# MCU.net
KiCad netlist of a schematic drawn in Altium Designer
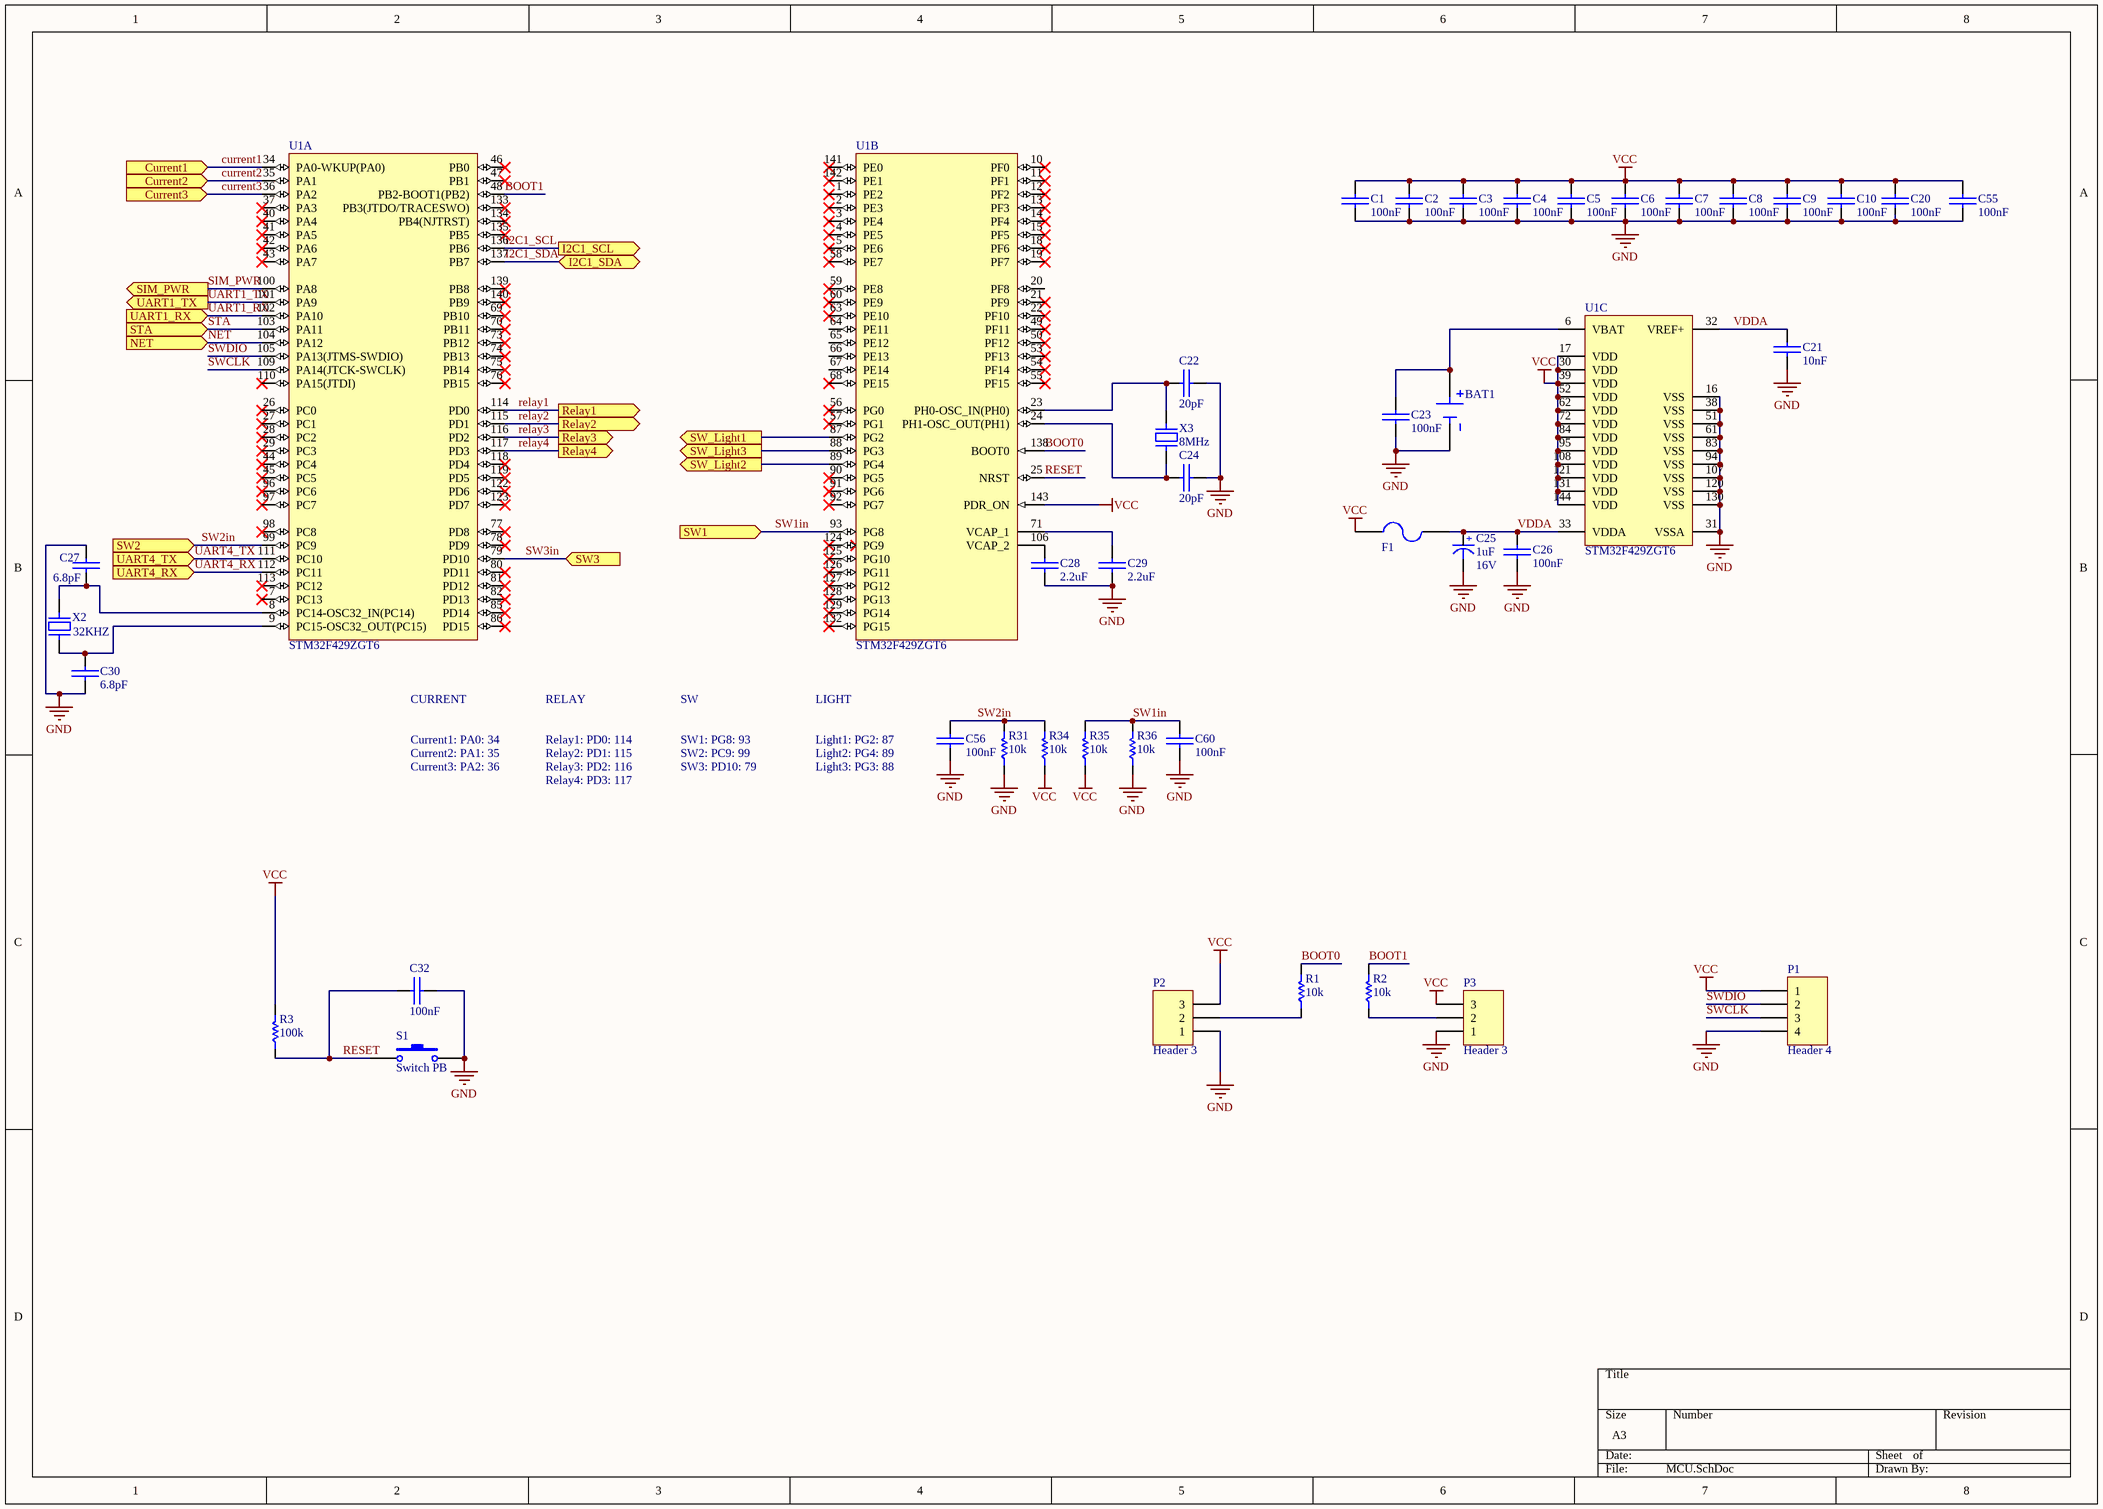
[diagram p0: MCU.SchDoc]

(export (version "E")
  (design (tool "Eeschema 10.0.6"))
  (components
    (comp (ref "BAT1")
      (value "BAT")
      (footprint "BAT_STAND")
      (description "BATTERY HOLDER COIN")
      (libsource (lib "SeyedMojtaba") (part "BAT"))
    )
    (comp (ref "C1")
      (value "100nF")
      (footprint "CAP 0603_1608")
      (description "Bipolar Capacitor")
      (fields (field (name "VOLTAGE") "100V") (field (name "DESIGNER") "Saeid Jorablo"))
      (libsource (lib "My_Library") (part "Cap-Bipolar"))
    )
    (comp (ref "C2")
      (value "100nF")
      (footprint "CAP 0603_1608")
      (description "Bipolar Capacitor")
      (fields (field (name "VOLTAGE") "100V") (field (name "DESIGNER") "Saeid Jorablo"))
      (libsource (lib "My_Library") (part "Cap-Bipolar"))
    )
    (comp (ref "C3")
      (value "100nF")
      (footprint "CAP 0603_1608")
      (description "Bipolar Capacitor")
      (fields (field (name "VOLTAGE") "100V") (field (name "DESIGNER") "Saeid Jorablo"))
      (libsource (lib "My_Library") (part "Cap-Bipolar"))
    )
    (comp (ref "C4")
      (value "100nF")
      (footprint "CAP 0603_1608")
      (description "Bipolar Capacitor")
      (fields (field (name "VOLTAGE") "100V") (field (name "DESIGNER") "Saeid Jorablo"))
      (libsource (lib "My_Library") (part "Cap-Bipolar"))
    )
    (comp (ref "C5")
      (value "100nF")
      (footprint "CAP 0603_1608")
      (description "Bipolar Capacitor")
      (fields (field (name "VOLTAGE") "100V") (field (name "DESIGNER") "Saeid Jorablo"))
      (libsource (lib "My_Library") (part "Cap-Bipolar"))
    )
    (comp (ref "C6")
      (value "100nF")
      (footprint "CAP 0603_1608")
      (description "Bipolar Capacitor")
      (fields (field (name "VOLTAGE") "100V") (field (name "DESIGNER") "Saeid Jorablo"))
      (libsource (lib "My_Library") (part "Cap-Bipolar"))
    )
    (comp (ref "C7")
      (value "100nF")
      (footprint "CAP 0603_1608")
      (description "Bipolar Capacitor")
      (fields (field (name "VOLTAGE") "100V") (field (name "DESIGNER") "Saeid Jorablo"))
      (libsource (lib "My_Library") (part "Cap-Bipolar"))
    )
    (comp (ref "C8")
      (value "100nF")
      (footprint "CAP 0603_1608")
      (description "Bipolar Capacitor")
      (fields (field (name "VOLTAGE") "100V") (field (name "DESIGNER") "Saeid Jorablo"))
      (libsource (lib "My_Library") (part "Cap-Bipolar"))
    )
    (comp (ref "C9")
      (value "100nF")
      (footprint "CAP 0603_1608")
      (description "Bipolar Capacitor")
      (fields (field (name "VOLTAGE") "100V") (field (name "DESIGNER") "Saeid Jorablo"))
      (libsource (lib "My_Library") (part "Cap-Bipolar"))
    )
    (comp (ref "C10")
      (value "100nF")
      (footprint "CAP 0603_1608")
      (description "Bipolar Capacitor")
      (fields (field (name "VOLTAGE") "100V") (field (name "DESIGNER") "Saeid Jorablo"))
      (libsource (lib "My_Library") (part "Cap-Bipolar"))
    )
    (comp (ref "C20")
      (value "100nF")
      (footprint "CAP 0603_1608")
      (description "Bipolar Capacitor")
      (fields (field (name "VOLTAGE") "100V") (field (name "DESIGNER") "Saeid Jorablo"))
      (libsource (lib "My_Library") (part "Cap-Bipolar"))
    )
    (comp (ref "C21")
      (value "10nF")
      (footprint "CAP 0603_1608")
      (description "Bipolar Capacitor")
      (fields (field (name "VOLTAGE") "100V") (field (name "DESIGNER") "Saeid Jorablo"))
      (libsource (lib "My_Library") (part "Cap-Bipolar"))
    )
    (comp (ref "C22")
      (value "20pF")
      (footprint "CAP 0805_2012")
      (description "Bipolar Capacitor")
      (fields (field (name "VOLTAGE") "100V") (field (name "DESIGNER") "Saeid Jorablo"))
      (libsource (lib "My_Library") (part "Cap-Bipolar"))
    )
    (comp (ref "C23")
      (value "100nF")
      (footprint "CAP 0603_1608")
      (description "Bipolar Capacitor")
      (fields (field (name "VOLTAGE") "100V") (field (name "DESIGNER") "Saeid Jorablo"))
      (libsource (lib "My_Library") (part "Cap-Bipolar"))
    )
    (comp (ref "C24")
      (value "20pF")
      (footprint "CAP 0805_2012")
      (description "Bipolar Capacitor")
      (fields (field (name "VOLTAGE") "100V") (field (name "DESIGNER") "Saeid Jorablo"))
      (libsource (lib "My_Library") (part "Cap-Bipolar"))
    )
    (comp (ref "C25")
      (value "1uF")
      (footprint "CAPP 1206 (3216X18L) Size A")
      (description "Polar Capacitor")
      (fields (field (name "VOLTAGE") "16V") (field (name "DESIGNER") "Saeid Jorablo"))
      (libsource (lib "My_Library") (part "Cap-Polar"))
    )
    (comp (ref "C26")
      (value "100nF")
      (footprint "CAP 0603_1608")
      (description "Bipolar Capacitor")
      (fields (field (name "VOLTAGE") "100V") (field (name "DESIGNER") "Saeid Jorablo"))
      (libsource (lib "My_Library") (part "Cap-Bipolar"))
    )
    (comp (ref "C27")
      (value "6.8pF")
      (footprint "CAP 0805_2012")
      (description "Bipolar Capacitor")
      (fields (field (name "VOLTAGE") "100V") (field (name "DESIGNER") "Saeid Jorablo"))
      (libsource (lib "My_Library") (part "Cap-Bipolar"))
    )
    (comp (ref "C28")
      (value "2.2uF")
      (footprint "CAP 0805_2012")
      (description "Bipolar Capacitor")
      (fields (field (name "VOLTAGE") "100V") (field (name "DESIGNER") "Saeid Jorablo"))
      (libsource (lib "My_Library") (part "Cap-Bipolar"))
    )
    (comp (ref "C29")
      (value "2.2uF")
      (footprint "CAP 0805_2012")
      (description "Bipolar Capacitor")
      (fields (field (name "VOLTAGE") "100V") (field (name "DESIGNER") "Saeid Jorablo"))
      (libsource (lib "My_Library") (part "Cap-Bipolar"))
    )
    (comp (ref "C30")
      (value "6.8pF")
      (footprint "CAP 0805_2012")
      (description "Bipolar Capacitor")
      (fields (field (name "VOLTAGE") "100V") (field (name "DESIGNER") "Saeid Jorablo"))
      (libsource (lib "My_Library") (part "Cap-Bipolar"))
    )
    (comp (ref "C32")
      (value "100nF")
      (footprint "CAP 0603_1608")
      (description "Bipolar Capacitor")
      (fields (field (name "VOLTAGE") "100V") (field (name "DESIGNER") "Saeid Jorablo"))
      (libsource (lib "My_Library") (part "Cap-Bipolar"))
    )
    (comp (ref "C55")
      (value "100nF")
      (footprint "CAP 0603_1608")
      (description "Bipolar Capacitor")
      (fields (field (name "VOLTAGE") "100V") (field (name "DESIGNER") "Saeid Jorablo"))
      (libsource (lib "My_Library") (part "Cap-Bipolar"))
    )
    (comp (ref "C56")
      (value "100nF")
      (footprint "CAP 0805_2012")
      (description "Bipolar Capacitor")
      (fields (field (name "VOLTAGE") "100V") (field (name "DESIGNER") "Saeid Jorablo"))
      (libsource (lib "My_Library") (part "Cap-Bipolar"))
    )
    (comp (ref "C60")
      (value "100nF")
      (footprint "CAP 0805_2012")
      (description "Bipolar Capacitor")
      (fields (field (name "VOLTAGE") "100V") (field (name "DESIGNER") "Saeid Jorablo"))
      (libsource (lib "My_Library") (part "Cap-Bipolar"))
    )
    (comp (ref "F1")
      (value "Ferrite Bead")
      (footprint "FUSE_0805")
      (libsource (lib "FUSE_FERRITE_VDR") (part "Fuse 0805"))
    )
    (comp (ref "P1")
      (value "Header 4")
      (footprint "HDR1X4")
      (description "Header, 4-Pin")
      (fields (field (name "PUBLISHER") "Altium Limited"))
      (libsource (lib "Miscellaneous Connectors") (part "Header 4"))
    )
    (comp (ref "P2")
      (value "Header 3")
      (footprint "HDR1X3")
      (description "Header, 3-Pin")
      (fields (field (name "PUBLISHER") "Altium Limited"))
      (libsource (lib "") (part "Header 3_1"))
    )
    (comp (ref "P3")
      (value "Header 3")
      (footprint "HDR1X3")
      (description "Header, 3-Pin")
      (fields (field (name "PUBLISHER") "Altium Limited"))
      (libsource (lib "Miscellaneous Connectors") (part "Header 3"))
    )
    (comp (ref "R1")
      (value "10k")
      (footprint "RES 0805_2012")
      (description "Resistor")
      (libsource (lib "My_Library") (part "Resistor"))
    )
    (comp (ref "R2")
      (value "10k")
      (footprint "RES 0805_2012")
      (description "Resistor")
      (libsource (lib "My_Library") (part "Resistor"))
    )
    (comp (ref "R3")
      (value "100k")
      (footprint "RES 0805_2012")
      (description "Resistor")
      (libsource (lib "My_Library") (part "Resistor"))
    )
    (comp (ref "R31")
      (value "10k")
      (footprint "RES 0805_2012")
      (description "Resistor")
      (libsource (lib "My_Library") (part "Resistor"))
    )
    (comp (ref "R34")
      (value "10k")
      (footprint "RES 0805_2012")
      (description "Resistor")
      (libsource (lib "My_Library") (part "Resistor"))
    )
    (comp (ref "R35")
      (value "10k")
      (footprint "RES 0805_2012")
      (description "Resistor")
      (libsource (lib "My_Library") (part "Resistor"))
    )
    (comp (ref "R36")
      (value "10k")
      (footprint "RES 0805_2012")
      (description "Resistor")
      (libsource (lib "My_Library") (part "Resistor"))
    )
    (comp (ref "S1")
      (value "Switch PB")
      (footprint "Switch - Push to On")
      (description "Push Button Switch")
      (libsource (lib "My_Library") (part "Switch PB"))
    )
    (comp (ref "U1")
      (value "STM32F429ZGT6")
      (footprint "LQFP144")
      (fields (field (name "MANUFACTURER") "STMicroelectronics"))
      (libsource (lib "MCU_MPU") (part "STM32F429ZGT6"))
    )
    (comp (ref "X2")
      (value "32KHZ")
      (footprint "IND 1206_3216")
      (description "SMT Crystal")
      (libsource (lib "Xtal") (part "Crystal HC-49S SMD"))
    )
    (comp (ref "X3")
      (value "~")
      (footprint "XTAL THD HC49")
      (description "SMT Crystal")
      (fields (field (name "PARAMETER 1") "8MHz"))
      (libsource (lib "CRYSTAL") (part "Crystal THD HC49"))
    )
  )
  (nets
    (net (code "1") (name "/BOOT0") (class "Default")
      (node (ref "R1") (pin "2") (pinfunction "2_2") (pintype "passive"))
      (node (ref "U1") (pin "138") (pinfunction "BOOT0_138") (pintype "input"))
    )
    (net (code "2") (name "/BOOT1") (class "Default")
      (node (ref "R2") (pin "2") (pinfunction "2_2") (pintype "passive"))
      (node (ref "U1") (pin "48") (pinfunction "PB2-BOOT1(PB2)_48") (pintype "bidirectional"))
    )
    (net (code "3") (name "/I2C1_SCL") (class "Default")
      (node (ref "U1") (pin "136") (pinfunction "PB6_136") (pintype "bidirectional"))
    )
    (net (code "4") (name "/I2C1_SDA") (class "Default")
      (node (ref "U1") (pin "137") (pinfunction "PB7_137") (pintype "bidirectional"))
    )
    (net (code "5") (name "/NET") (class "Default")
      (node (ref "U1") (pin "104") (pinfunction "PA12_104") (pintype "bidirectional"))
    )
    (net (code "6") (name "/RESET") (class "Default")
      (node (ref "C32") (pin "2") (pinfunction "-_2") (pintype "passive"))
      (node (ref "R3") (pin "1") (pinfunction "1_1") (pintype "passive"))
      (node (ref "S1") (pin "1") (pinfunction "1_1") (pintype "passive"))
      (node (ref "U1") (pin "25") (pinfunction "NRST_25") (pintype "bidirectional"))
    )
    (net (code "7") (name "/SIM_PWR") (class "Default")
      (node (ref "U1") (pin "100") (pinfunction "PA8_100") (pintype "bidirectional"))
    )
    (net (code "8") (name "/STA") (class "Default")
      (node (ref "U1") (pin "103") (pinfunction "PA11_103") (pintype "bidirectional"))
    )
    (net (code "9") (name "/SW1in") (class "Default")
      (node (ref "C60") (pin "2") (pinfunction "-_2") (pintype "passive"))
      (node (ref "R35") (pin "2") (pinfunction "2_2") (pintype "passive"))
      (node (ref "R36") (pin "2") (pinfunction "2_2") (pintype "passive"))
      (node (ref "U1") (pin "93") (pinfunction "PG8_93") (pintype "bidirectional"))
    )
    (net (code "10") (name "/SW2in") (class "Default")
      (node (ref "C56") (pin "2") (pinfunction "-_2") (pintype "passive"))
      (node (ref "R31") (pin "2") (pinfunction "2_2") (pintype "passive"))
      (node (ref "R34") (pin "2") (pinfunction "2_2") (pintype "passive"))
      (node (ref "U1") (pin "99") (pinfunction "PC9_99") (pintype "bidirectional"))
    )
    (net (code "11") (name "/SW3in") (class "Default")
      (node (ref "U1") (pin "79") (pinfunction "PD10_79") (pintype "bidirectional"))
    )
    (net (code "12") (name "/SWCLK") (class "Default")
      (node (ref "P1") (pin "3") (pinfunction "3_3") (pintype "passive"))
      (node (ref "U1") (pin "109") (pinfunction "PA14(JTCK-SWCLK)_109") (pintype "bidirectional"))
    )
    (net (code "13") (name "/SWDIO") (class "Default")
      (node (ref "P1") (pin "2") (pinfunction "2_2") (pintype "passive"))
      (node (ref "U1") (pin "105") (pinfunction "PA13(JTMS-SWDIO)_105") (pintype "bidirectional"))
    )
    (net (code "14") (name "/SW_Light1") (class "Default")
      (node (ref "U1") (pin "87") (pinfunction "PG2_87") (pintype "bidirectional"))
    )
    (net (code "15") (name "/SW_Light2") (class "Default")
      (node (ref "U1") (pin "89") (pinfunction "PG4_89") (pintype "bidirectional"))
    )
    (net (code "16") (name "/SW_Light3") (class "Default")
      (node (ref "U1") (pin "88") (pinfunction "PG3_88") (pintype "bidirectional"))
    )
    (net (code "17") (name "/UART1_RX") (class "Default")
      (node (ref "U1") (pin "102") (pinfunction "PA10_102") (pintype "bidirectional"))
    )
    (net (code "18") (name "/UART1_TX") (class "Default")
      (node (ref "U1") (pin "101") (pinfunction "PA9_101") (pintype "bidirectional"))
    )
    (net (code "19") (name "/UART4_RX") (class "Default")
      (node (ref "U1") (pin "112") (pinfunction "PC11_112") (pintype "bidirectional"))
    )
    (net (code "20") (name "/UART4_TX") (class "Default")
      (node (ref "U1") (pin "111") (pinfunction "PC10_111") (pintype "bidirectional"))
    )
    (net (code "21") (name "/VDDA") (class "Default")
      (node (ref "C21") (pin "2") (pinfunction "-_2") (pintype "passive"))
      (node (ref "C25") (pin "1") (pinfunction "+_1") (pintype "passive"))
      (node (ref "C26") (pin "2") (pinfunction "-_2") (pintype "passive"))
      (node (ref "F1") (pin "2") (pinfunction "2_2") (pintype "passive"))
      (node (ref "U1") (pin "32") (pinfunction "VREF+_32") (pintype "power_in"))
      (node (ref "U1") (pin "33") (pinfunction "VDDA_33") (pintype "power_in"))
    )
    (net (code "22") (name "/current1") (class "Default")
      (node (ref "U1") (pin "34") (pinfunction "PA0-WKUP(PA0)_34") (pintype "bidirectional"))
    )
    (net (code "23") (name "/current2") (class "Default")
      (node (ref "U1") (pin "35") (pinfunction "PA1_35") (pintype "bidirectional"))
    )
    (net (code "24") (name "/current3") (class "Default")
      (node (ref "U1") (pin "36") (pinfunction "PA2_36") (pintype "bidirectional"))
    )
    (net (code "25") (name "/relay1") (class "Default")
      (node (ref "U1") (pin "114") (pinfunction "PD0_114") (pintype "bidirectional"))
    )
    (net (code "26") (name "/relay2") (class "Default")
      (node (ref "U1") (pin "115") (pinfunction "PD1_115") (pintype "bidirectional"))
    )
    (net (code "27") (name "/relay3") (class "Default")
      (node (ref "U1") (pin "116") (pinfunction "PD2_116") (pintype "bidirectional"))
    )
    (net (code "28") (name "/relay4") (class "Default")
      (node (ref "U1") (pin "117") (pinfunction "PD3_117") (pintype "bidirectional"))
    )
    (net (code "29") (name "GND") (class "Default")
      (node (ref "BAT1") (pin "NEG") (pinfunction "NEG_NEG") (pintype "power_in"))
      (node (ref "C1") (pin "1") (pinfunction "+_1") (pintype "passive"))
      (node (ref "C10") (pin "1") (pinfunction "+_1") (pintype "passive"))
      (node (ref "C2") (pin "1") (pinfunction "+_1") (pintype "passive"))
      (node (ref "C20") (pin "1") (pinfunction "+_1") (pintype "passive"))
      (node (ref "C21") (pin "1") (pinfunction "+_1") (pintype "passive"))
      (node (ref "C22") (pin "1") (pinfunction "+_1") (pintype "passive"))
      (node (ref "C23") (pin "1") (pinfunction "+_1") (pintype "passive"))
      (node (ref "C24") (pin "1") (pinfunction "+_1") (pintype "passive"))
      (node (ref "C25") (pin "2") (pinfunction "-_2") (pintype "passive"))
      (node (ref "C26") (pin "1") (pinfunction "+_1") (pintype "passive"))
      (node (ref "C27") (pin "1") (pinfunction "+_1") (pintype "passive"))
      (node (ref "C28") (pin "1") (pinfunction "+_1") (pintype "passive"))
      (node (ref "C29") (pin "1") (pinfunction "+_1") (pintype "passive"))
      (node (ref "C3") (pin "1") (pinfunction "+_1") (pintype "passive"))
      (node (ref "C30") (pin "2") (pinfunction "-_2") (pintype "passive"))
      (node (ref "C32") (pin "1") (pinfunction "+_1") (pintype "passive"))
      (node (ref "C4") (pin "1") (pinfunction "+_1") (pintype "passive"))
      (node (ref "C5") (pin "1") (pinfunction "+_1") (pintype "passive"))
      (node (ref "C55") (pin "1") (pinfunction "+_1") (pintype "passive"))
      (node (ref "C56") (pin "1") (pinfunction "+_1") (pintype "passive"))
      (node (ref "C6") (pin "1") (pinfunction "+_1") (pintype "passive"))
      (node (ref "C60") (pin "1") (pinfunction "+_1") (pintype "passive"))
      (node (ref "C7") (pin "1") (pinfunction "+_1") (pintype "passive"))
      (node (ref "C8") (pin "1") (pinfunction "+_1") (pintype "passive"))
      (node (ref "C9") (pin "1") (pinfunction "+_1") (pintype "passive"))
      (node (ref "P1") (pin "4") (pinfunction "4_4") (pintype "passive"))
      (node (ref "P2") (pin "1") (pinfunction "1_1") (pintype "passive"))
      (node (ref "P3") (pin "1") (pinfunction "1_1") (pintype "passive"))
      (node (ref "R31") (pin "1") (pinfunction "1_1") (pintype "passive"))
      (node (ref "R36") (pin "1") (pinfunction "1_1") (pintype "passive"))
      (node (ref "S1") (pin "2") (pinfunction "2_2") (pintype "passive"))
      (node (ref "U1") (pin "107") (pinfunction "VSS_107") (pintype "power_in"))
      (node (ref "U1") (pin "120") (pinfunction "VSS_120") (pintype "power_in"))
      (node (ref "U1") (pin "130") (pinfunction "VSS_130") (pintype "power_in"))
      (node (ref "U1") (pin "16") (pinfunction "VSS_16") (pintype "power_in"))
      (node (ref "U1") (pin "31") (pinfunction "VSSA_31") (pintype "power_in"))
      (node (ref "U1") (pin "38") (pinfunction "VSS_38") (pintype "power_in"))
      (node (ref "U1") (pin "51") (pinfunction "VSS_51") (pintype "power_in"))
      (node (ref "U1") (pin "61") (pinfunction "VSS_61") (pintype "power_in"))
      (node (ref "U1") (pin "83") (pinfunction "VSS_83") (pintype "power_in"))
      (node (ref "U1") (pin "94") (pinfunction "VSS_94") (pintype "power_in"))
    )
    (net (code "30") (name "Net-(C22--)") (class "Default")
      (node (ref "C22") (pin "2") (pinfunction "-_2") (pintype "passive"))
      (node (ref "U1") (pin "23") (pinfunction "PH0-OSC_IN(PH0)_23") (pintype "bidirectional"))
      (node (ref "X3") (pin "2") (pinfunction "2_2") (pintype "passive"))
    )
    (net (code "31") (name "Net-(C23--)") (class "Default")
      (node (ref "BAT1") (pin "S+1") (pinfunction "POS_S+1") (pintype "passive"))
      (node (ref "BAT1") (pin "S+2") (pinfunction "POS_S+2") (pintype "power_in"))
      (node (ref "C23") (pin "2") (pinfunction "-_2") (pintype "passive"))
      (node (ref "U1") (pin "6") (pinfunction "VBAT_6") (pintype "power_in"))
    )
    (net (code "32") (name "Net-(C24--)") (class "Default")
      (node (ref "C24") (pin "2") (pinfunction "-_2") (pintype "passive"))
      (node (ref "U1") (pin "24") (pinfunction "PH1-OSC_OUT(PH1)_24") (pintype "bidirectional"))
      (node (ref "X3") (pin "1") (pinfunction "1_1") (pintype "passive"))
    )
    (net (code "33") (name "Net-(C27--)") (class "Default")
      (node (ref "C27") (pin "2") (pinfunction "-_2") (pintype "passive"))
      (node (ref "U1") (pin "8") (pinfunction "PC14-OSC32_IN(PC14)_8") (pintype "bidirectional"))
      (node (ref "X2") (pin "2") (pinfunction "2_2") (pintype "passive"))
    )
    (net (code "34") (name "Net-(C28--)") (class "Default")
      (node (ref "C28") (pin "2") (pinfunction "-_2") (pintype "passive"))
      (node (ref "U1") (pin "106") (pinfunction "VCAP_2_106") (pintype "power_in"))
    )
    (net (code "35") (name "Net-(C29--)") (class "Default")
      (node (ref "C29") (pin "2") (pinfunction "-_2") (pintype "passive"))
      (node (ref "U1") (pin "71") (pinfunction "VCAP_1_71") (pintype "power_in"))
    )
    (net (code "36") (name "Net-(C30-+)") (class "Default")
      (node (ref "C30") (pin "1") (pinfunction "+_1") (pintype "passive"))
      (node (ref "U1") (pin "9") (pinfunction "PC15-OSC32_OUT(PC15)_9") (pintype "bidirectional"))
      (node (ref "X2") (pin "1") (pinfunction "1_1") (pintype "passive"))
    )
    (net (code "37") (name "Net-(P2-Pad2)") (class "Default")
      (node (ref "P2") (pin "2") (pinfunction "2_2") (pintype "passive"))
      (node (ref "R1") (pin "1") (pinfunction "1_1") (pintype "passive"))
    )
    (net (code "38") (name "Net-(P3-Pad2)") (class "Default")
      (node (ref "P3") (pin "2") (pinfunction "2_2") (pintype "passive"))
      (node (ref "R2") (pin "1") (pinfunction "1_1") (pintype "passive"))
    )
    (net (code "39") (name "VCC") (class "Default")
      (node (ref "C1") (pin "2") (pinfunction "-_2") (pintype "passive"))
      (node (ref "C10") (pin "2") (pinfunction "-_2") (pintype "passive"))
      (node (ref "C2") (pin "2") (pinfunction "-_2") (pintype "passive"))
      (node (ref "C20") (pin "2") (pinfunction "-_2") (pintype "passive"))
      (node (ref "C3") (pin "2") (pinfunction "-_2") (pintype "passive"))
      (node (ref "C4") (pin "2") (pinfunction "-_2") (pintype "passive"))
      (node (ref "C5") (pin "2") (pinfunction "-_2") (pintype "passive"))
      (node (ref "C55") (pin "2") (pinfunction "-_2") (pintype "passive"))
      (node (ref "C6") (pin "2") (pinfunction "-_2") (pintype "passive"))
      (node (ref "C7") (pin "2") (pinfunction "-_2") (pintype "passive"))
      (node (ref "C8") (pin "2") (pinfunction "-_2") (pintype "passive"))
      (node (ref "C9") (pin "2") (pinfunction "-_2") (pintype "passive"))
      (node (ref "F1") (pin "1") (pinfunction "1_1") (pintype "passive"))
      (node (ref "P1") (pin "1") (pinfunction "1_1") (pintype "passive"))
      (node (ref "P2") (pin "3") (pinfunction "3_3") (pintype "passive"))
      (node (ref "P3") (pin "3") (pinfunction "3_3") (pintype "passive"))
      (node (ref "R3") (pin "2") (pinfunction "2_2") (pintype "passive"))
      (node (ref "R34") (pin "1") (pinfunction "1_1") (pintype "passive"))
      (node (ref "R35") (pin "1") (pinfunction "1_1") (pintype "passive"))
      (node (ref "U1") (pin "108") (pinfunction "VDD_108") (pintype "power_in"))
      (node (ref "U1") (pin "121") (pinfunction "VDD_121") (pintype "power_in"))
      (node (ref "U1") (pin "131") (pinfunction "VDD_131") (pintype "power_in"))
      (node (ref "U1") (pin "143") (pinfunction "PDR_ON_143") (pintype "input"))
      (node (ref "U1") (pin "144") (pinfunction "VDD_144") (pintype "power_in"))
      (node (ref "U1") (pin "17") (pinfunction "VDD_17") (pintype "power_in"))
      (node (ref "U1") (pin "30") (pinfunction "VDD_30") (pintype "power_in"))
      (node (ref "U1") (pin "39") (pinfunction "VDD_39") (pintype "power_in"))
      (node (ref "U1") (pin "52") (pinfunction "VDD_52") (pintype "power_in"))
      (node (ref "U1") (pin "62") (pinfunction "VDD_62") (pintype "power_in"))
      (node (ref "U1") (pin "72") (pinfunction "VDD_72") (pintype "power_in"))
      (node (ref "U1") (pin "84") (pinfunction "VDD_84") (pintype "power_in"))
      (node (ref "U1") (pin "95") (pinfunction "VDD_95") (pintype "power_in"))
    )
    (net (code "40") (name "unconnected-(U1A-PA3-Pad37)") (class "Default")
      (node (ref "U1") (pin "37") (pinfunction "PA3_37") (pintype "bidirectional+no_connect"))
    )
    (net (code "41") (name "unconnected-(U1A-PA4-Pad40)") (class "Default")
      (node (ref "U1") (pin "40") (pinfunction "PA4_40") (pintype "bidirectional+no_connect"))
    )
    (net (code "42") (name "unconnected-(U1A-PA5-Pad41)") (class "Default")
      (node (ref "U1") (pin "41") (pinfunction "PA5_41") (pintype "bidirectional+no_connect"))
    )
    (net (code "43") (name "unconnected-(U1A-PA6-Pad42)") (class "Default")
      (node (ref "U1") (pin "42") (pinfunction "PA6_42") (pintype "bidirectional+no_connect"))
    )
    (net (code "44") (name "unconnected-(U1A-PA7-Pad43)") (class "Default")
      (node (ref "U1") (pin "43") (pinfunction "PA7_43") (pintype "bidirectional+no_connect"))
    )
    (net (code "45") (name "unconnected-(U1A-PA15(JTDI)-Pad110)") (class "Default")
      (node (ref "U1") (pin "110") (pinfunction "PA15(JTDI)_110") (pintype "bidirectional+no_connect"))
    )
    (net (code "46") (name "unconnected-(U1A-PB0-Pad46)") (class "Default")
      (node (ref "U1") (pin "46") (pinfunction "PB0_46") (pintype "bidirectional+no_connect"))
    )
    (net (code "47") (name "unconnected-(U1A-PB1-Pad47)") (class "Default")
      (node (ref "U1") (pin "47") (pinfunction "PB1_47") (pintype "bidirectional+no_connect"))
    )
    (net (code "48") (name "unconnected-(U1A-PB3(JTDO{slash}TRACESWO)-Pad133)") (class "Default")
      (node (ref "U1") (pin "133") (pinfunction "PB3(JTDO/TRACESWO)_133") (pintype "bidirectional+no_connect"))
    )
    (net (code "49") (name "unconnected-(U1A-PB4(NJTRST)-Pad134)") (class "Default")
      (node (ref "U1") (pin "134") (pinfunction "PB4(NJTRST)_134") (pintype "bidirectional+no_connect"))
    )
    (net (code "50") (name "unconnected-(U1A-PB5-Pad135)") (class "Default")
      (node (ref "U1") (pin "135") (pinfunction "PB5_135") (pintype "bidirectional+no_connect"))
    )
    (net (code "51") (name "unconnected-(U1A-PB8-Pad139)") (class "Default")
      (node (ref "U1") (pin "139") (pinfunction "PB8_139") (pintype "bidirectional+no_connect"))
    )
    (net (code "52") (name "unconnected-(U1A-PB9-Pad140)") (class "Default")
      (node (ref "U1") (pin "140") (pinfunction "PB9_140") (pintype "bidirectional+no_connect"))
    )
    (net (code "53") (name "unconnected-(U1A-PB10-Pad69)") (class "Default")
      (node (ref "U1") (pin "69") (pinfunction "PB10_69") (pintype "bidirectional+no_connect"))
    )
    (net (code "54") (name "unconnected-(U1A-PB11-Pad70)") (class "Default")
      (node (ref "U1") (pin "70") (pinfunction "PB11_70") (pintype "bidirectional+no_connect"))
    )
    (net (code "55") (name "unconnected-(U1A-PB12-Pad73)") (class "Default")
      (node (ref "U1") (pin "73") (pinfunction "PB12_73") (pintype "bidirectional+no_connect"))
    )
    (net (code "56") (name "unconnected-(U1A-PB13-Pad74)") (class "Default")
      (node (ref "U1") (pin "74") (pinfunction "PB13_74") (pintype "bidirectional+no_connect"))
    )
    (net (code "57") (name "unconnected-(U1A-PB14-Pad75)") (class "Default")
      (node (ref "U1") (pin "75") (pinfunction "PB14_75") (pintype "bidirectional+no_connect"))
    )
    (net (code "58") (name "unconnected-(U1A-PB15-Pad76)") (class "Default")
      (node (ref "U1") (pin "76") (pinfunction "PB15_76") (pintype "bidirectional+no_connect"))
    )
    (net (code "59") (name "unconnected-(U1A-PC0-Pad26)") (class "Default")
      (node (ref "U1") (pin "26") (pinfunction "PC0_26") (pintype "bidirectional+no_connect"))
    )
    (net (code "60") (name "unconnected-(U1A-PC1-Pad27)") (class "Default")
      (node (ref "U1") (pin "27") (pinfunction "PC1_27") (pintype "bidirectional+no_connect"))
    )
    (net (code "61") (name "unconnected-(U1A-PC2-Pad28)") (class "Default")
      (node (ref "U1") (pin "28") (pinfunction "PC2_28") (pintype "bidirectional+no_connect"))
    )
    (net (code "62") (name "unconnected-(U1A-PC3-Pad29)") (class "Default")
      (node (ref "U1") (pin "29") (pinfunction "PC3_29") (pintype "bidirectional+no_connect"))
    )
    (net (code "63") (name "unconnected-(U1A-PC4-Pad44)") (class "Default")
      (node (ref "U1") (pin "44") (pinfunction "PC4_44") (pintype "bidirectional+no_connect"))
    )
    (net (code "64") (name "unconnected-(U1A-PC5-Pad45)") (class "Default")
      (node (ref "U1") (pin "45") (pinfunction "PC5_45") (pintype "bidirectional+no_connect"))
    )
    (net (code "65") (name "unconnected-(U1A-PC6-Pad96)") (class "Default")
      (node (ref "U1") (pin "96") (pinfunction "PC6_96") (pintype "bidirectional+no_connect"))
    )
    (net (code "66") (name "unconnected-(U1A-PC7-Pad97)") (class "Default")
      (node (ref "U1") (pin "97") (pinfunction "PC7_97") (pintype "bidirectional+no_connect"))
    )
    (net (code "67") (name "unconnected-(U1A-PC8-Pad98)") (class "Default")
      (node (ref "U1") (pin "98") (pinfunction "PC8_98") (pintype "bidirectional+no_connect"))
    )
    (net (code "68") (name "unconnected-(U1A-PC12-Pad113)") (class "Default")
      (node (ref "U1") (pin "113") (pinfunction "PC12_113") (pintype "bidirectional+no_connect"))
    )
    (net (code "69") (name "unconnected-(U1A-PC13-Pad7)") (class "Default")
      (node (ref "U1") (pin "7") (pinfunction "PC13_7") (pintype "bidirectional+no_connect"))
    )
    (net (code "70") (name "unconnected-(U1A-PD4-Pad118)") (class "Default")
      (node (ref "U1") (pin "118") (pinfunction "PD4_118") (pintype "bidirectional+no_connect"))
    )
    (net (code "71") (name "unconnected-(U1A-PD5-Pad119)") (class "Default")
      (node (ref "U1") (pin "119") (pinfunction "PD5_119") (pintype "bidirectional+no_connect"))
    )
    (net (code "72") (name "unconnected-(U1A-PD6-Pad122)") (class "Default")
      (node (ref "U1") (pin "122") (pinfunction "PD6_122") (pintype "bidirectional+no_connect"))
    )
    (net (code "73") (name "unconnected-(U1A-PD7-Pad123)") (class "Default")
      (node (ref "U1") (pin "123") (pinfunction "PD7_123") (pintype "bidirectional+no_connect"))
    )
    (net (code "74") (name "unconnected-(U1A-PD8-Pad77)") (class "Default")
      (node (ref "U1") (pin "77") (pinfunction "PD8_77") (pintype "bidirectional+no_connect"))
    )
    (net (code "75") (name "unconnected-(U1A-PD9-Pad78)") (class "Default")
      (node (ref "U1") (pin "78") (pinfunction "PD9_78") (pintype "bidirectional+no_connect"))
    )
    (net (code "76") (name "unconnected-(U1A-PD11-Pad80)") (class "Default")
      (node (ref "U1") (pin "80") (pinfunction "PD11_80") (pintype "bidirectional+no_connect"))
    )
    (net (code "77") (name "unconnected-(U1A-PD12-Pad81)") (class "Default")
      (node (ref "U1") (pin "81") (pinfunction "PD12_81") (pintype "bidirectional+no_connect"))
    )
    (net (code "78") (name "unconnected-(U1A-PD13-Pad82)") (class "Default")
      (node (ref "U1") (pin "82") (pinfunction "PD13_82") (pintype "bidirectional+no_connect"))
    )
    (net (code "79") (name "unconnected-(U1A-PD14-Pad85)") (class "Default")
      (node (ref "U1") (pin "85") (pinfunction "PD14_85") (pintype "bidirectional+no_connect"))
    )
    (net (code "80") (name "unconnected-(U1A-PD15-Pad86)") (class "Default")
      (node (ref "U1") (pin "86") (pinfunction "PD15_86") (pintype "bidirectional+no_connect"))
    )
    (net (code "81") (name "unconnected-(U1B-PE0-Pad141)") (class "Default")
      (node (ref "U1") (pin "141") (pinfunction "PE0_141") (pintype "bidirectional+no_connect"))
    )
    (net (code "82") (name "unconnected-(U1B-PE1-Pad142)") (class "Default")
      (node (ref "U1") (pin "142") (pinfunction "PE1_142") (pintype "bidirectional+no_connect"))
    )
    (net (code "83") (name "unconnected-(U1B-PE2-Pad1)") (class "Default")
      (node (ref "U1") (pin "1") (pinfunction "PE2_1") (pintype "bidirectional+no_connect"))
    )
    (net (code "84") (name "unconnected-(U1B-PE3-Pad2)") (class "Default")
      (node (ref "U1") (pin "2") (pinfunction "PE3_2") (pintype "bidirectional+no_connect"))
    )
    (net (code "85") (name "unconnected-(U1B-PE4-Pad3)") (class "Default")
      (node (ref "U1") (pin "3") (pinfunction "PE4_3") (pintype "bidirectional+no_connect"))
    )
    (net (code "86") (name "unconnected-(U1B-PE5-Pad4)") (class "Default")
      (node (ref "U1") (pin "4") (pinfunction "PE5_4") (pintype "bidirectional+no_connect"))
    )
    (net (code "87") (name "unconnected-(U1B-PE6-Pad5)") (class "Default")
      (node (ref "U1") (pin "5") (pinfunction "PE6_5") (pintype "bidirectional+no_connect"))
    )
    (net (code "88") (name "unconnected-(U1B-PE7-Pad58)") (class "Default")
      (node (ref "U1") (pin "58") (pinfunction "PE7_58") (pintype "bidirectional+no_connect"))
    )
    (net (code "89") (name "unconnected-(U1B-PE8-Pad59)") (class "Default")
      (node (ref "U1") (pin "59") (pinfunction "PE8_59") (pintype "bidirectional+no_connect"))
    )
    (net (code "90") (name "unconnected-(U1B-PE9-Pad60)") (class "Default")
      (node (ref "U1") (pin "60") (pinfunction "PE9_60") (pintype "bidirectional+no_connect"))
    )
    (net (code "91") (name "unconnected-(U1B-PE10-Pad63)") (class "Default")
      (node (ref "U1") (pin "63") (pinfunction "PE10_63") (pintype "bidirectional+no_connect"))
    )
    (net (code "92") (name "unconnected-(U1B-PE11-Pad64)") (class "Default")
      (node (ref "U1") (pin "64") (pinfunction "PE11_64") (pintype "bidirectional"))
    )
    (net (code "93") (name "unconnected-(U1B-PE12-Pad65)") (class "Default")
      (node (ref "U1") (pin "65") (pinfunction "PE12_65") (pintype "bidirectional"))
    )
    (net (code "94") (name "unconnected-(U1B-PE13-Pad66)") (class "Default")
      (node (ref "U1") (pin "66") (pinfunction "PE13_66") (pintype "bidirectional"))
    )
    (net (code "95") (name "unconnected-(U1B-PE14-Pad67)") (class "Default")
      (node (ref "U1") (pin "67") (pinfunction "PE14_67") (pintype "bidirectional"))
    )
    (net (code "96") (name "unconnected-(U1B-PE15-Pad68)") (class "Default")
      (node (ref "U1") (pin "68") (pinfunction "PE15_68") (pintype "bidirectional+no_connect"))
    )
    (net (code "97") (name "unconnected-(U1B-PF0-Pad10)") (class "Default")
      (node (ref "U1") (pin "10") (pinfunction "PF0_10") (pintype "bidirectional+no_connect"))
    )
    (net (code "98") (name "unconnected-(U1B-PF1-Pad11)") (class "Default")
      (node (ref "U1") (pin "11") (pinfunction "PF1_11") (pintype "bidirectional+no_connect"))
    )
    (net (code "99") (name "unconnected-(U1B-PF2-Pad12)") (class "Default")
      (node (ref "U1") (pin "12") (pinfunction "PF2_12") (pintype "bidirectional+no_connect"))
    )
    (net (code "100") (name "unconnected-(U1B-PF3-Pad13)") (class "Default")
      (node (ref "U1") (pin "13") (pinfunction "PF3_13") (pintype "bidirectional+no_connect"))
    )
    (net (code "101") (name "unconnected-(U1B-PF4-Pad14)") (class "Default")
      (node (ref "U1") (pin "14") (pinfunction "PF4_14") (pintype "bidirectional+no_connect"))
    )
    (net (code "102") (name "unconnected-(U1B-PF5-Pad15)") (class "Default")
      (node (ref "U1") (pin "15") (pinfunction "PF5_15") (pintype "bidirectional+no_connect"))
    )
    (net (code "103") (name "unconnected-(U1B-PF6-Pad18)") (class "Default")
      (node (ref "U1") (pin "18") (pinfunction "PF6_18") (pintype "bidirectional+no_connect"))
    )
    (net (code "104") (name "unconnected-(U1B-PF7-Pad19)") (class "Default")
      (node (ref "U1") (pin "19") (pinfunction "PF7_19") (pintype "bidirectional+no_connect"))
    )
    (net (code "105") (name "unconnected-(U1B-PF8-Pad20)") (class "Default")
      (node (ref "U1") (pin "20") (pinfunction "PF8_20") (pintype "bidirectional"))
    )
    (net (code "106") (name "unconnected-(U1B-PF9-Pad21)") (class "Default")
      (node (ref "U1") (pin "21") (pinfunction "PF9_21") (pintype "bidirectional+no_connect"))
    )
    (net (code "107") (name "unconnected-(U1B-PF10-Pad22)") (class "Default")
      (node (ref "U1") (pin "22") (pinfunction "PF10_22") (pintype "bidirectional+no_connect"))
    )
    (net (code "108") (name "unconnected-(U1B-PF11-Pad49)") (class "Default")
      (node (ref "U1") (pin "49") (pinfunction "PF11_49") (pintype "bidirectional+no_connect"))
    )
    (net (code "109") (name "unconnected-(U1B-PF12-Pad50)") (class "Default")
      (node (ref "U1") (pin "50") (pinfunction "PF12_50") (pintype "bidirectional+no_connect"))
    )
    (net (code "110") (name "unconnected-(U1B-PF13-Pad53)") (class "Default")
      (node (ref "U1") (pin "53") (pinfunction "PF13_53") (pintype "bidirectional+no_connect"))
    )
    (net (code "111") (name "unconnected-(U1B-PF14-Pad54)") (class "Default")
      (node (ref "U1") (pin "54") (pinfunction "PF14_54") (pintype "bidirectional+no_connect"))
    )
    (net (code "112") (name "unconnected-(U1B-PF15-Pad55)") (class "Default")
      (node (ref "U1") (pin "55") (pinfunction "PF15_55") (pintype "bidirectional+no_connect"))
    )
    (net (code "113") (name "unconnected-(U1B-PG0-Pad56)") (class "Default")
      (node (ref "U1") (pin "56") (pinfunction "PG0_56") (pintype "bidirectional+no_connect"))
    )
    (net (code "114") (name "unconnected-(U1B-PG1-Pad57)") (class "Default")
      (node (ref "U1") (pin "57") (pinfunction "PG1_57") (pintype "bidirectional+no_connect"))
    )
    (net (code "115") (name "unconnected-(U1B-PG5-Pad90)") (class "Default")
      (node (ref "U1") (pin "90") (pinfunction "PG5_90") (pintype "bidirectional+no_connect"))
    )
    (net (code "116") (name "unconnected-(U1B-PG6-Pad91)") (class "Default")
      (node (ref "U1") (pin "91") (pinfunction "PG6_91") (pintype "bidirectional+no_connect"))
    )
    (net (code "117") (name "unconnected-(U1B-PG7-Pad92)") (class "Default")
      (node (ref "U1") (pin "92") (pinfunction "PG7_92") (pintype "bidirectional+no_connect"))
    )
    (net (code "118") (name "unconnected-(U1B-PG9-Pad124)") (class "Default")
      (node (ref "U1") (pin "124") (pinfunction "PG9_124") (pintype "bidirectional+no_connect"))
    )
    (net (code "119") (name "unconnected-(U1B-PG10-Pad125)") (class "Default")
      (node (ref "U1") (pin "125") (pinfunction "PG10_125") (pintype "bidirectional+no_connect"))
    )
    (net (code "120") (name "unconnected-(U1B-PG11-Pad126)") (class "Default")
      (node (ref "U1") (pin "126") (pinfunction "PG11_126") (pintype "bidirectional+no_connect"))
    )
    (net (code "121") (name "unconnected-(U1B-PG12-Pad127)") (class "Default")
      (node (ref "U1") (pin "127") (pinfunction "PG12_127") (pintype "bidirectional+no_connect"))
    )
    (net (code "122") (name "unconnected-(U1B-PG13-Pad128)") (class "Default")
      (node (ref "U1") (pin "128") (pinfunction "PG13_128") (pintype "bidirectional+no_connect"))
    )
    (net (code "123") (name "unconnected-(U1B-PG14-Pad129)") (class "Default")
      (node (ref "U1") (pin "129") (pinfunction "PG14_129") (pintype "bidirectional+no_connect"))
    )
    (net (code "124") (name "unconnected-(U1B-PG15-Pad132)") (class "Default")
      (node (ref "U1") (pin "132") (pinfunction "PG15_132") (pintype "bidirectional+no_connect"))
    )
  )
)
